# hijack-fram_B.net
KiCad netlist of a schematic drawn in EAGLE
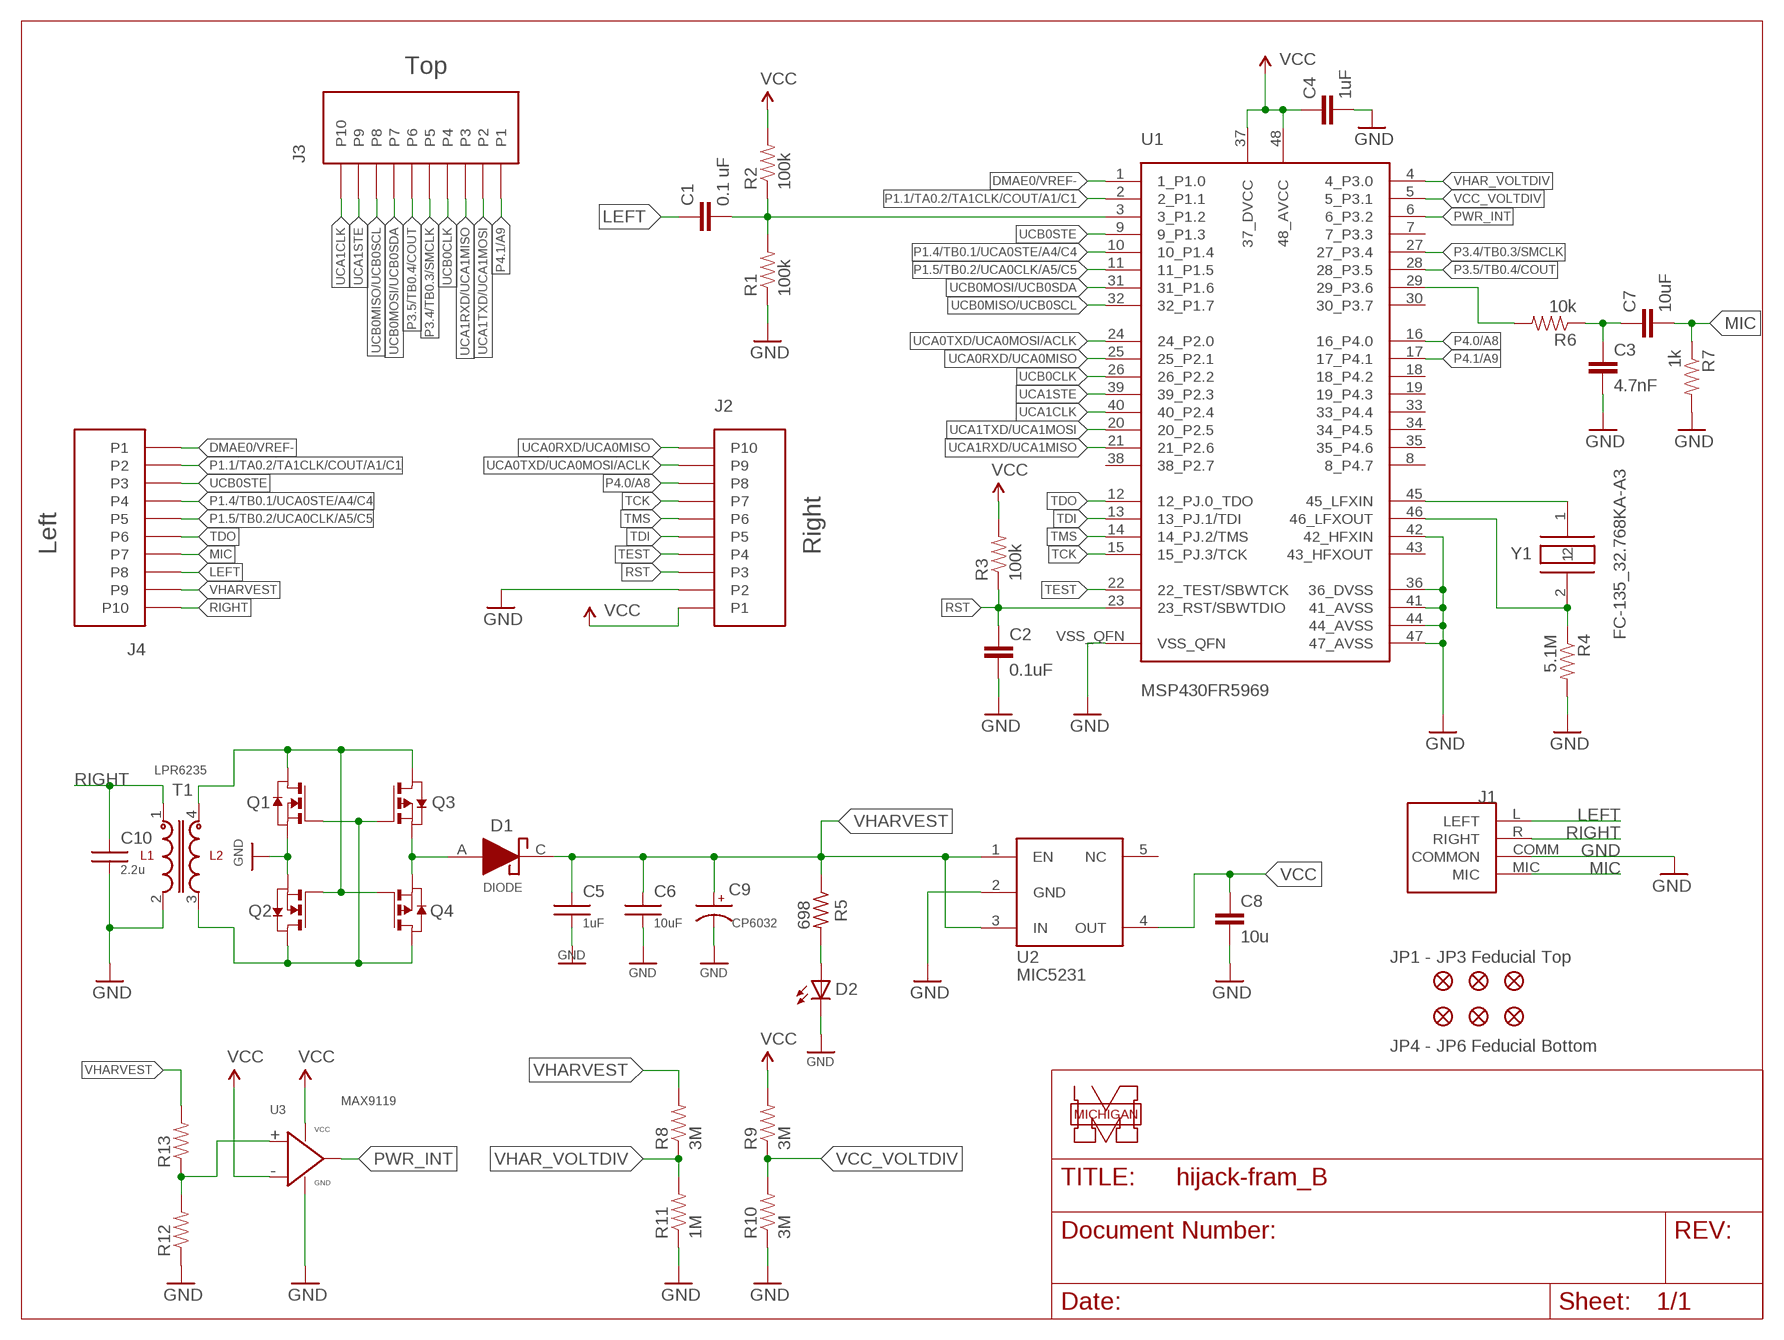
[diagram p0: schematic, sheet 1]

(export (version "E")
  (design (tool "Eeschema 10.0.6"))
  (components
    (comp (ref "C1")
      (value "0.1 uF")
      (footprint "eagle-import:0603-CAP")
      (libsource (lib "eagle-import") (part "CAP0603-CAP"))
    )
    (comp (ref "C2")
      (value "0.1uF")
      (footprint "eagle-import:0603-CAP")
      (libsource (lib "eagle-import") (part "CAP0603-CAP"))
    )
    (comp (ref "C3")
      (value "4.7nF")
      (footprint "eagle-import:0603-CAP")
      (libsource (lib "eagle-import") (part "CAP0603-CAP"))
    )
    (comp (ref "C4")
      (value "1uF")
      (footprint "eagle-import:0603-CAP")
      (libsource (lib "eagle-import") (part "CAP0603-CAP"))
    )
    (comp (ref "C5")
      (value "1uF")
      (footprint "eagle-import:C0603")
      (libsource (lib "eagle-import") (part "C0603"))
    )
    (comp (ref "C6")
      (value "10uF")
      (footprint "eagle-import:C0603")
      (libsource (lib "eagle-import") (part "C0603"))
    )
    (comp (ref "C7")
      (value "10uF")
      (footprint "eagle-import:0603-CAP")
      (libsource (lib "eagle-import") (part "CAP0603-CAP"))
    )
    (comp (ref "C8")
      (value "10u")
      (footprint "eagle-import:C0603")
      (libsource (lib "eagle-import") (part "C-EUC0603"))
    )
    (comp (ref "C9")
      (value "CP6032")
      (footprint "eagle-import:CT6032")
      (libsource (lib "eagle-import") (part "CP6032"))
    )
    (comp (ref "C10")
      (value "2.2u")
      (footprint "eagle-import:C0603")
      (libsource (lib "eagle-import") (part "C0603"))
    )
    (comp (ref "D1")
      (value "DIODE")
      (footprint "eagle-import:MINIMELF")
      (libsource (lib "eagle-import") (part "DIODE"))
    )
    (comp (ref "D2")
      (value "LED0603")
      (footprint "eagle-import:LED-0603")
      (libsource (lib "eagle-import") (part "LED0603"))
    )
    (comp (ref "J1")
      (value "3.5JACK4CONNSUNSTONE_QUICKTURN")
      (footprint "eagle-import:PLUGBOARDCONNECTOR_SUNSTONE")
      (libsource (lib "eagle-import") (part "3.5JACK4CONNSUNSTONE_QUICKTURN"))
    )
    (comp (ref "J2")
      (value "HEADER10POS")
      (footprint "eagle-import:10PIN2MMHEADER")
      (libsource (lib "eagle-import") (part "HEADER10POS"))
    )
    (comp (ref "J3")
      (value "HEADER10POS")
      (footprint "eagle-import:10PIN2MMHEADER")
      (libsource (lib "eagle-import") (part "HEADER10POS"))
    )
    (comp (ref "J4")
      (value "HEADER10POS")
      (footprint "eagle-import:10PIN2MMHEADER")
      (libsource (lib "eagle-import") (part "HEADER10POS"))
    )
    (comp (ref "JP1")
      (value "FIDUCIAL1X2")
      (footprint "eagle-import:FIDUCIAL-1X2")
      (libsource (lib "eagle-import") (part "FIDUCIAL1X2"))
    )
    (comp (ref "JP2")
      (value "FIDUCIAL1X2")
      (footprint "eagle-import:FIDUCIAL-1X2")
      (libsource (lib "eagle-import") (part "FIDUCIAL1X2"))
    )
    (comp (ref "JP3")
      (value "FIDUCIAL1X2")
      (footprint "eagle-import:FIDUCIAL-1X2")
      (libsource (lib "eagle-import") (part "FIDUCIAL1X2"))
    )
    (comp (ref "JP4")
      (value "FIDUCIAL1X2")
      (footprint "eagle-import:FIDUCIAL-1X2")
      (libsource (lib "eagle-import") (part "FIDUCIAL1X2"))
    )
    (comp (ref "JP5")
      (value "FIDUCIAL1X2")
      (footprint "eagle-import:FIDUCIAL-1X2")
      (libsource (lib "eagle-import") (part "FIDUCIAL1X2"))
    )
    (comp (ref "JP6")
      (value "FIDUCIAL1X2")
      (footprint "eagle-import:FIDUCIAL-1X2")
      (libsource (lib "eagle-import") (part "FIDUCIAL1X2"))
    )
    (comp (ref "Q1")
      (value "NMOSSOT23")
      (footprint "eagle-import:SOT-23")
      (libsource (lib "eagle-import") (part "NMOSSOT23"))
    )
    (comp (ref "Q2")
      (value "NMOSSOT23")
      (footprint "eagle-import:SOT-23")
      (libsource (lib "eagle-import") (part "NMOSSOT23"))
    )
    (comp (ref "Q3")
      (value "PMOSSOT23")
      (footprint "eagle-import:SOT-23")
      (libsource (lib "eagle-import") (part "PMOSSOT23"))
    )
    (comp (ref "Q4")
      (value "PMOSSOT23")
      (footprint "eagle-import:SOT-23")
      (libsource (lib "eagle-import") (part "PMOSSOT23"))
    )
    (comp (ref "R1")
      (value "100k")
      (footprint "eagle-import:0603-RES")
      (libsource (lib "eagle-import") (part "RESISTOR0603-RES"))
    )
    (comp (ref "R2")
      (value "100k")
      (footprint "eagle-import:0603-RES")
      (libsource (lib "eagle-import") (part "RESISTOR0603-RES"))
    )
    (comp (ref "R3")
      (value "100k")
      (footprint "eagle-import:0603-RES")
      (libsource (lib "eagle-import") (part "RESISTOR0603-RES"))
    )
    (comp (ref "R4")
      (value "5.1M")
      (footprint "eagle-import:0603-RES")
      (libsource (lib "eagle-import") (part "RESISTOR0603-RES"))
    )
    (comp (ref "R5")
      (value "698")
      (footprint "eagle-import:R0603")
      (libsource (lib "eagle-import") (part "R-US_R0603"))
    )
    (comp (ref "R6")
      (value "10k")
      (footprint "eagle-import:0603-RES")
      (libsource (lib "eagle-import") (part "RESISTOR0603-RES"))
    )
    (comp (ref "R7")
      (value "1k")
      (footprint "eagle-import:0603-RES")
      (libsource (lib "eagle-import") (part "RESISTOR0603-RES"))
    )
    (comp (ref "R8")
      (value "3M")
      (footprint "eagle-import:0603-RES")
      (libsource (lib "eagle-import") (part "RESISTOR0603-RES"))
    )
    (comp (ref "R9")
      (value "3M")
      (footprint "eagle-import:0603-RES")
      (libsource (lib "eagle-import") (part "RESISTOR0603-RES"))
    )
    (comp (ref "R10")
      (value "3M")
      (footprint "eagle-import:0603-RES")
      (libsource (lib "eagle-import") (part "RESISTOR0603-RES"))
    )
    (comp (ref "R11")
      (value "1M")
      (footprint "eagle-import:0603-RES")
      (libsource (lib "eagle-import") (part "RESISTOR0603-RES"))
    )
    (comp (ref "R12")
      (value "RESISTOR0603-RES")
      (footprint "eagle-import:0603-RES")
      (libsource (lib "eagle-import") (part "RESISTOR0603-RES"))
    )
    (comp (ref "R13")
      (value "RESISTOR0603-RES")
      (footprint "eagle-import:0603-RES")
      (libsource (lib "eagle-import") (part "RESISTOR0603-RES"))
    )
    (comp (ref "T1")
      (value "LPR6235")
      (footprint "eagle-import:LPR6235")
      (libsource (lib "eagle-import") (part "LPR6235"))
    )
    (comp (ref "U1")
      (value "MSP430FR5969")
      (footprint "eagle-import:RGZ(S-PQFP-N48)")
      (libsource (lib "eagle-import") (part "MSP430FR5969"))
    )
    (comp (ref "U2")
      (value "MIC5231")
      (footprint "eagle-import:SOT23-5")
      (libsource (lib "eagle-import") (part "MIC5231"))
    )
    (comp (ref "U3")
      (value "MAX9119")
      (footprint "eagle-import:SC70-5")
      (libsource (lib "eagle-import") (part "MAX9119"))
    )
    (comp (ref "Y1")
      (value "FC-135_32.768KA-A3")
      (footprint "eagle-import:FC-135")
      (libsource (lib "eagle-import") (part "FC-135_32.768KA-A3"))
    )
  )
  (nets
    (net (code "1") (name "DMAE0{slash}VREF-") (class "Default")
      (node (ref "J4") (pin "P1") (pinfunction "P1_P1") (pintype "bidirectional"))
      (node (ref "U1") (pin "1") (pinfunction "1_P1.0_1") (pintype "bidirectional"))
    )
    (net (code "2") (name "GND") (class "Default")
      (node (ref "C10") (pin "2") (pinfunction "2_2") (pintype "bidirectional"))
      (node (ref "C2") (pin "2") (pinfunction "2_2") (pintype "passive"))
      (node (ref "C3") (pin "2") (pinfunction "2_2") (pintype "passive"))
      (node (ref "C4") (pin "2") (pinfunction "2_2") (pintype "passive"))
      (node (ref "C5") (pin "2") (pinfunction "2_2") (pintype "bidirectional"))
      (node (ref "C6") (pin "2") (pinfunction "2_2") (pintype "bidirectional"))
      (node (ref "C8") (pin "2") (pinfunction "2_2") (pintype "passive"))
      (node (ref "C9") (pin "-") (pinfunction "-_-") (pintype "bidirectional"))
      (node (ref "D2") (pin "C") (pinfunction "C_C") (pintype "passive"))
      (node (ref "J1") (pin "COMM") (pinfunction "COMMON_COMM") (pintype "power_in"))
      (node (ref "J2") (pin "P2") (pinfunction "P2_P2") (pintype "bidirectional"))
      (node (ref "Q1") (pin "2") (pinfunction "S_2") (pintype "passive"))
      (node (ref "Q2") (pin "2") (pinfunction "S_2") (pintype "passive"))
      (node (ref "R1") (pin "1") (pinfunction "1_1") (pintype "passive"))
      (node (ref "R10") (pin "1") (pinfunction "1_1") (pintype "passive"))
      (node (ref "R11") (pin "1") (pinfunction "1_1") (pintype "passive"))
      (node (ref "R12") (pin "1") (pinfunction "1_1") (pintype "passive"))
      (node (ref "R4") (pin "2") (pinfunction "2_2") (pintype "passive"))
      (node (ref "R7") (pin "2") (pinfunction "2_2") (pintype "passive"))
      (node (ref "T1") (pin "2") (pinfunction "2_2") (pintype "bidirectional"))
      (node (ref "U1") (pin "36") (pinfunction "36_DVSS_36") (pintype "bidirectional"))
      (node (ref "U1") (pin "41") (pinfunction "41_AVSS_41") (pintype "bidirectional"))
      (node (ref "U1") (pin "42") (pinfunction "42_HFXIN_42") (pintype "bidirectional"))
      (node (ref "U1") (pin "44") (pinfunction "44_AVSS_44") (pintype "bidirectional"))
      (node (ref "U1") (pin "47") (pinfunction "47_AVSS_47") (pintype "bidirectional"))
      (node (ref "U1") (pin "VSS_QFN") (pinfunction "VSS_QFN_VSS_QFN") (pintype "bidirectional"))
      (node (ref "U2") (pin "2") (pinfunction "GND_2") (pintype "bidirectional"))
      (node (ref "U3") (pin "2") (pinfunction "GND_2") (pintype "bidirectional"))
    )
    (net (code "3") (name "LEFT") (class "Default")
      (node (ref "C1") (pin "1") (pinfunction "1_1") (pintype "passive"))
      (node (ref "J1") (pin "L") (pinfunction "LEFT_L") (pintype "output"))
      (node (ref "J4") (pin "P8") (pinfunction "P8_P8") (pintype "bidirectional"))
    )
    (net (code "4") (name "MIC") (class "Default")
      (node (ref "C7") (pin "2") (pinfunction "2_2") (pintype "passive"))
      (node (ref "J1") (pin "MIC") (pinfunction "MIC_MIC") (pintype "input"))
      (node (ref "J4") (pin "P7") (pinfunction "P7_P7") (pintype "bidirectional"))
      (node (ref "R7") (pin "1") (pinfunction "1_1") (pintype "passive"))
    )
    (net (code "5") (name "Net-(C3-Pad1)") (class "Default")
      (node (ref "C3") (pin "1") (pinfunction "1_1") (pintype "passive"))
      (node (ref "C7") (pin "1") (pinfunction "1_1") (pintype "passive"))
      (node (ref "R6") (pin "1") (pinfunction "1_1") (pintype "passive"))
    )
    (net (code "6") (name "Net-(D2-PadA)") (class "Default")
      (node (ref "D2") (pin "A") (pinfunction "A_A") (pintype "passive"))
      (node (ref "R5") (pin "2") (pinfunction "2_2") (pintype "passive"))
    )
    (net (code "7") (name "Net-(Q1-D)") (class "Default")
      (node (ref "Q1") (pin "1") (pinfunction "D_1") (pintype "passive"))
      (node (ref "Q2") (pin "3") (pinfunction "G_3") (pintype "passive"))
      (node (ref "Q3") (pin "1") (pinfunction "D_1") (pintype "passive"))
      (node (ref "Q4") (pin "3") (pinfunction "G_3") (pintype "passive"))
      (node (ref "T1") (pin "4") (pinfunction "4_4") (pintype "bidirectional"))
    )
    (net (code "8") (name "Net-(Q1-G)") (class "Default")
      (node (ref "Q1") (pin "3") (pinfunction "G_3") (pintype "passive"))
      (node (ref "Q2") (pin "1") (pinfunction "D_1") (pintype "passive"))
      (node (ref "Q3") (pin "3") (pinfunction "G_3") (pintype "passive"))
      (node (ref "Q4") (pin "1") (pinfunction "D_1") (pintype "passive"))
      (node (ref "T1") (pin "3") (pinfunction "3_3") (pintype "bidirectional"))
    )
    (net (code "9") (name "Net-(Q3-S)") (class "Default")
      (node (ref "D1") (pin "A") (pinfunction "A_A") (pintype "bidirectional"))
      (node (ref "Q3") (pin "2") (pinfunction "S_2") (pintype "passive"))
      (node (ref "Q4") (pin "2") (pinfunction "S_2") (pintype "passive"))
    )
    (net (code "10") (name "Net-(U1-3_P1.2)") (class "Default")
      (node (ref "C1") (pin "2") (pinfunction "2_2") (pintype "passive"))
      (node (ref "R1") (pin "2") (pinfunction "2_2") (pintype "passive"))
      (node (ref "R2") (pin "1") (pinfunction "1_1") (pintype "passive"))
      (node (ref "U1") (pin "3") (pinfunction "3_P1.2_3") (pintype "bidirectional"))
    )
    (net (code "11") (name "Net-(U1-29_P3.6)") (class "Default")
      (node (ref "R6") (pin "2") (pinfunction "2_2") (pintype "passive"))
      (node (ref "U1") (pin "29") (pinfunction "29_P3.6_29") (pintype "bidirectional"))
    )
    (net (code "12") (name "Net-(U1-45_LFXIN)") (class "Default")
      (node (ref "U1") (pin "45") (pinfunction "45_LFXIN_45") (pintype "bidirectional"))
      (node (ref "Y1") (pin "1") (pinfunction "1_1") (pintype "bidirectional"))
    )
    (net (code "13") (name "Net-(U1-46_LFXOUT)") (class "Default")
      (node (ref "R4") (pin "1") (pinfunction "1_1") (pintype "passive"))
      (node (ref "U1") (pin "46") (pinfunction "46_LFXOUT_46") (pintype "bidirectional"))
      (node (ref "Y1") (pin "2") (pinfunction "2_2") (pintype "bidirectional"))
    )
    (net (code "14") (name "Net-(U3-IN+)") (class "Default")
      (node (ref "R12") (pin "2") (pinfunction "2_2") (pintype "passive"))
      (node (ref "R13") (pin "1") (pinfunction "1_1") (pintype "passive"))
      (node (ref "U3") (pin "3") (pinfunction "IN+_3") (pintype "bidirectional"))
    )
    (net (code "15") (name "P1.1{slash}TA0.2{slash}TA1CLK{slash}COUT{slash}A1{slash}C1") (class "Default")
      (node (ref "J4") (pin "P2") (pinfunction "P2_P2") (pintype "bidirectional"))
      (node (ref "U1") (pin "2") (pinfunction "2_P1.1_2") (pintype "bidirectional"))
    )
    (net (code "16") (name "P1.4{slash}TB0.1{slash}UCA0STE{slash}A4{slash}C4") (class "Default")
      (node (ref "J4") (pin "P4") (pinfunction "P4_P4") (pintype "bidirectional"))
      (node (ref "U1") (pin "10") (pinfunction "10_P1.4_10") (pintype "bidirectional"))
    )
    (net (code "17") (name "P1.5{slash}TB0.2{slash}UCA0CLK{slash}A5{slash}C5") (class "Default")
      (node (ref "J4") (pin "P5") (pinfunction "P5_P5") (pintype "bidirectional"))
      (node (ref "U1") (pin "11") (pinfunction "11_P1.5_11") (pintype "bidirectional"))
    )
    (net (code "18") (name "P3.4{slash}TB0.3{slash}SMCLK") (class "Default")
      (node (ref "J3") (pin "P5") (pinfunction "P5_P5") (pintype "bidirectional"))
      (node (ref "U1") (pin "27") (pinfunction "27_P3.4_27") (pintype "bidirectional"))
    )
    (net (code "19") (name "P3.5{slash}TB0.4{slash}COUT") (class "Default")
      (node (ref "J3") (pin "P6") (pinfunction "P6_P6") (pintype "bidirectional"))
      (node (ref "U1") (pin "28") (pinfunction "28_P3.5_28") (pintype "bidirectional"))
    )
    (net (code "20") (name "P4.0{slash}A8") (class "Default")
      (node (ref "J2") (pin "P8") (pinfunction "P8_P8") (pintype "bidirectional"))
      (node (ref "U1") (pin "16") (pinfunction "16_P4.0_16") (pintype "bidirectional"))
    )
    (net (code "21") (name "P4.1{slash}A9") (class "Default")
      (node (ref "J3") (pin "P1") (pinfunction "P1_P1") (pintype "bidirectional"))
      (node (ref "U1") (pin "17") (pinfunction "17_P4.1_17") (pintype "bidirectional"))
    )
    (net (code "22") (name "PWR_INT") (class "Default")
      (node (ref "U1") (pin "6") (pinfunction "6_P3.2_6") (pintype "bidirectional"))
      (node (ref "U3") (pin "1") (pinfunction "OUT_1") (pintype "bidirectional"))
    )
    (net (code "23") (name "RIGHT") (class "Default")
      (node (ref "C10") (pin "1") (pinfunction "1_1") (pintype "bidirectional"))
      (node (ref "J1") (pin "R") (pinfunction "RIGHT_R") (pintype "output"))
      (node (ref "J4") (pin "P10") (pinfunction "P10_P10") (pintype "bidirectional"))
      (node (ref "T1") (pin "1") (pinfunction "1_1") (pintype "bidirectional"))
    )
    (net (code "24") (name "RST") (class "Default")
      (node (ref "C2") (pin "1") (pinfunction "1_1") (pintype "passive"))
      (node (ref "J2") (pin "P3") (pinfunction "P3_P3") (pintype "bidirectional"))
      (node (ref "R3") (pin "1") (pinfunction "1_1") (pintype "passive"))
      (node (ref "U1") (pin "23") (pinfunction "23_RST/SBWTDIO_23") (pintype "bidirectional"))
    )
    (net (code "25") (name "TCK") (class "Default")
      (node (ref "J2") (pin "P7") (pinfunction "P7_P7") (pintype "bidirectional"))
      (node (ref "U1") (pin "15") (pinfunction "15_PJ.3/TCK_15") (pintype "bidirectional"))
    )
    (net (code "26") (name "TDI") (class "Default")
      (node (ref "J2") (pin "P5") (pinfunction "P5_P5") (pintype "bidirectional"))
      (node (ref "U1") (pin "13") (pinfunction "13_PJ.1/TDI_13") (pintype "bidirectional"))
    )
    (net (code "27") (name "TDO") (class "Default")
      (node (ref "J4") (pin "P6") (pinfunction "P6_P6") (pintype "bidirectional"))
      (node (ref "U1") (pin "12") (pinfunction "12_PJ.0_TDO_12") (pintype "bidirectional"))
    )
    (net (code "28") (name "TEST") (class "Default")
      (node (ref "J2") (pin "P4") (pinfunction "P4_P4") (pintype "bidirectional"))
      (node (ref "U1") (pin "22") (pinfunction "22_TEST/SBWTCK_22") (pintype "bidirectional"))
    )
    (net (code "29") (name "TMS") (class "Default")
      (node (ref "J2") (pin "P6") (pinfunction "P6_P6") (pintype "bidirectional"))
      (node (ref "U1") (pin "14") (pinfunction "14_PJ.2/TMS_14") (pintype "bidirectional"))
    )
    (net (code "30") (name "UCA0RXD{slash}UCA0MISO") (class "Default")
      (node (ref "J2") (pin "P10") (pinfunction "P10_P10") (pintype "bidirectional"))
      (node (ref "U1") (pin "25") (pinfunction "25_P2.1_25") (pintype "bidirectional"))
    )
    (net (code "31") (name "UCA0TXD{slash}UCA0MOSI{slash}ACLK") (class "Default")
      (node (ref "J2") (pin "P9") (pinfunction "P9_P9") (pintype "bidirectional"))
      (node (ref "U1") (pin "24") (pinfunction "24_P2.0_24") (pintype "bidirectional"))
    )
    (net (code "32") (name "UCA1CLK") (class "Default")
      (node (ref "J3") (pin "P10") (pinfunction "P10_P10") (pintype "bidirectional"))
      (node (ref "U1") (pin "40") (pinfunction "40_P2.4_40") (pintype "bidirectional"))
    )
    (net (code "33") (name "UCA1RXD{slash}UCA1MISO") (class "Default")
      (node (ref "J3") (pin "P3") (pinfunction "P3_P3") (pintype "bidirectional"))
      (node (ref "U1") (pin "21") (pinfunction "21_P2.6_21") (pintype "bidirectional"))
    )
    (net (code "34") (name "UCA1STE") (class "Default")
      (node (ref "J3") (pin "P9") (pinfunction "P9_P9") (pintype "bidirectional"))
      (node (ref "U1") (pin "39") (pinfunction "39_P2.3_39") (pintype "bidirectional"))
    )
    (net (code "35") (name "UCA1TXD{slash}UCA1MOSI") (class "Default")
      (node (ref "J3") (pin "P2") (pinfunction "P2_P2") (pintype "bidirectional"))
      (node (ref "U1") (pin "20") (pinfunction "20_P2.5_20") (pintype "bidirectional"))
    )
    (net (code "36") (name "UCB0CLK") (class "Default")
      (node (ref "J3") (pin "P4") (pinfunction "P4_P4") (pintype "bidirectional"))
      (node (ref "U1") (pin "26") (pinfunction "26_P2.2_26") (pintype "bidirectional"))
    )
    (net (code "37") (name "UCB0MISO{slash}UCB0SCL") (class "Default")
      (node (ref "J3") (pin "P8") (pinfunction "P8_P8") (pintype "bidirectional"))
      (node (ref "U1") (pin "32") (pinfunction "32_P1.7_32") (pintype "bidirectional"))
    )
    (net (code "38") (name "UCB0MOSI{slash}UCB0SDA") (class "Default")
      (node (ref "J3") (pin "P7") (pinfunction "P7_P7") (pintype "bidirectional"))
      (node (ref "U1") (pin "31") (pinfunction "31_P1.6_31") (pintype "bidirectional"))
    )
    (net (code "39") (name "UCB0STE") (class "Default")
      (node (ref "J4") (pin "P3") (pinfunction "P3_P3") (pintype "bidirectional"))
      (node (ref "U1") (pin "9") (pinfunction "9_P1.3_9") (pintype "bidirectional"))
    )
    (net (code "40") (name "VCC") (class "Default")
      (node (ref "C4") (pin "1") (pinfunction "1_1") (pintype "passive"))
      (node (ref "C8") (pin "1") (pinfunction "1_1") (pintype "passive"))
      (node (ref "J2") (pin "P1") (pinfunction "P1_P1") (pintype "bidirectional"))
      (node (ref "R2") (pin "2") (pinfunction "2_2") (pintype "passive"))
      (node (ref "R3") (pin "2") (pinfunction "2_2") (pintype "passive"))
      (node (ref "R9") (pin "2") (pinfunction "2_2") (pintype "passive"))
      (node (ref "U1") (pin "37") (pinfunction "37_DVCC_37") (pintype "bidirectional"))
      (node (ref "U1") (pin "48") (pinfunction "48_AVCC_48") (pintype "bidirectional"))
      (node (ref "U2") (pin "4") (pinfunction "OUT_4") (pintype "bidirectional"))
      (node (ref "U3") (pin "4") (pinfunction "IN-_4") (pintype "bidirectional"))
      (node (ref "U3") (pin "5") (pinfunction "VCC_5") (pintype "bidirectional"))
    )
    (net (code "41") (name "VCC_VOLTDIV") (class "Default")
      (node (ref "R10") (pin "2") (pinfunction "2_2") (pintype "passive"))
      (node (ref "R9") (pin "1") (pinfunction "1_1") (pintype "passive"))
      (node (ref "U1") (pin "5") (pinfunction "5_P3.1_5") (pintype "bidirectional"))
    )
    (net (code "42") (name "VHARVEST") (class "Default")
      (node (ref "C5") (pin "1") (pinfunction "1_1") (pintype "bidirectional"))
      (node (ref "C6") (pin "1") (pinfunction "1_1") (pintype "bidirectional"))
      (node (ref "C9") (pin "+") (pinfunction "+_+") (pintype "bidirectional"))
      (node (ref "D1") (pin "C") (pinfunction "C_C") (pintype "bidirectional"))
      (node (ref "J4") (pin "P9") (pinfunction "P9_P9") (pintype "bidirectional"))
      (node (ref "R13") (pin "2") (pinfunction "2_2") (pintype "passive"))
      (node (ref "R5") (pin "1") (pinfunction "1_1") (pintype "passive"))
      (node (ref "R8") (pin "2") (pinfunction "2_2") (pintype "passive"))
      (node (ref "U2") (pin "1") (pinfunction "EN_1") (pintype "bidirectional"))
      (node (ref "U2") (pin "3") (pinfunction "IN_3") (pintype "bidirectional"))
    )
    (net (code "43") (name "VHAR_VOLTDIV") (class "Default")
      (node (ref "R11") (pin "2") (pinfunction "2_2") (pintype "passive"))
      (node (ref "R8") (pin "1") (pinfunction "1_1") (pintype "passive"))
      (node (ref "U1") (pin "4") (pinfunction "4_P3.0_4") (pintype "bidirectional"))
    )
    (net (code "44") (name "unconnected-(U1-7_P3.3-Pad7)") (class "Default")
      (node (ref "U1") (pin "7") (pinfunction "7_P3.3_7") (pintype "bidirectional"))
    )
    (net (code "45") (name "unconnected-(U1-8_P4.7-Pad8)") (class "Default")
      (node (ref "U1") (pin "8") (pinfunction "8_P4.7_8") (pintype "bidirectional"))
    )
    (net (code "46") (name "unconnected-(U1-18_P4.2-Pad18)") (class "Default")
      (node (ref "U1") (pin "18") (pinfunction "18_P4.2_18") (pintype "bidirectional"))
    )
    (net (code "47") (name "unconnected-(U1-19_P4.3-Pad19)") (class "Default")
      (node (ref "U1") (pin "19") (pinfunction "19_P4.3_19") (pintype "bidirectional"))
    )
    (net (code "48") (name "unconnected-(U1-30_P3.7-Pad30)") (class "Default")
      (node (ref "U1") (pin "30") (pinfunction "30_P3.7_30") (pintype "bidirectional"))
    )
    (net (code "49") (name "unconnected-(U1-33_P4.4-Pad33)") (class "Default")
      (node (ref "U1") (pin "33") (pinfunction "33_P4.4_33") (pintype "bidirectional"))
    )
    (net (code "50") (name "unconnected-(U1-34_P4.5-Pad34)") (class "Default")
      (node (ref "U1") (pin "34") (pinfunction "34_P4.5_34") (pintype "bidirectional"))
    )
    (net (code "51") (name "unconnected-(U1-35_P4.6-Pad35)") (class "Default")
      (node (ref "U1") (pin "35") (pinfunction "35_P4.6_35") (pintype "bidirectional"))
    )
    (net (code "52") (name "unconnected-(U1-38_P2.7-Pad38)") (class "Default")
      (node (ref "U1") (pin "38") (pinfunction "38_P2.7_38") (pintype "bidirectional"))
    )
    (net (code "53") (name "unconnected-(U1-43_HFXOUT-Pad43)") (class "Default")
      (node (ref "U1") (pin "43") (pinfunction "43_HFXOUT_43") (pintype "bidirectional"))
    )
    (net (code "54") (name "unconnected-(U2-NC-Pad5)") (class "Default")
      (node (ref "U2") (pin "5") (pinfunction "NC_5") (pintype "bidirectional"))
    )
  )
)
